# SCH_PHOENIX_-_PCB-3.net
KiCad netlist of a schematic drawn in EasyEDA
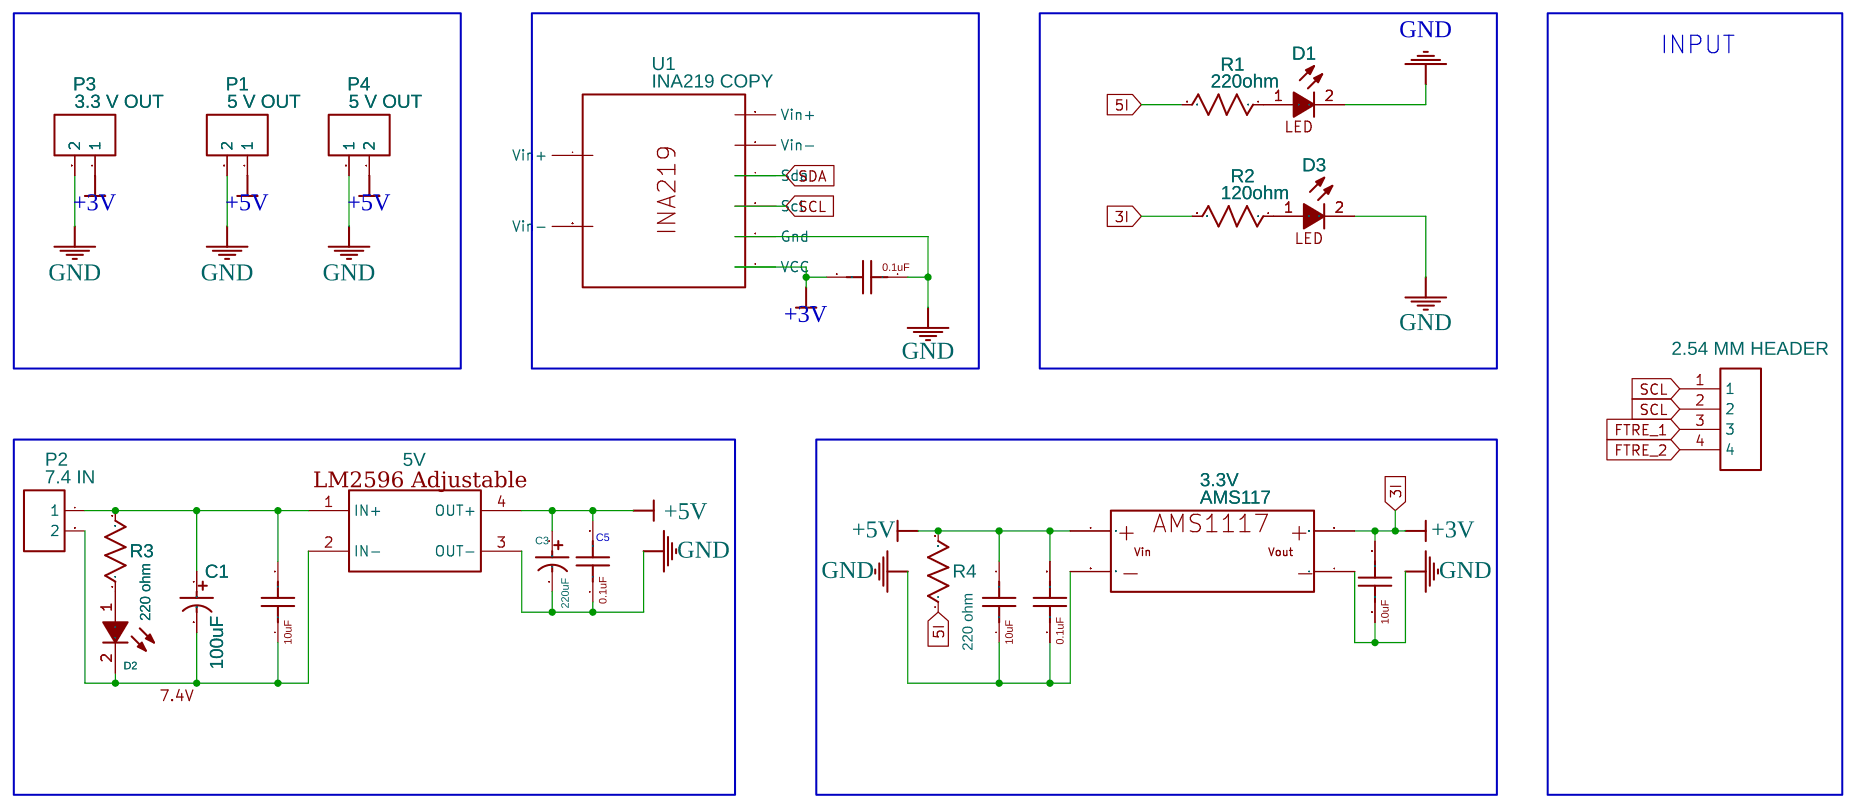
[diagram p0: schematic sheet]

(export (version "E")
  (design (tool "Eeschema 10.0.6"))
  (components
    (comp (ref "3.3V") (value "AMS117") (libsource (lib "") (part "AMS117")))
    (comp (ref "5V") (value "LM2596 ADJ COPY") (libsource (lib "") (part "BuckConverters_LM2596_Adj")))
    (comp (ref "C1")
      (value "100uF")
      (fields
        (field (name "Manufacturer Part") "KM476M016D11RR0VH2FP0")
        (field (name "Manufacturer") "CX(承兴)")
      )
      (libsource (lib "") (part "capacitor 680uF"))
    )
    (comp (ref "C2") (value "22PF CERAMIC CAPACITOR") (libsource (lib "") (part "22PF CERAMIC CAPACITOR")))
    (comp (ref "C3")
      (value "220uF")
      (fields
        (field (name "Manufacturer Part") "KM476M016D11RR0VH2FP0")
        (field (name "Manufacturer") "CX(承兴)")
      )
      (libsource (lib "") (part "capacitor 680uF"))
    )
    (comp (ref "C4") (value "22PF CERAMIC CAPACITOR") (libsource (lib "") (part "22PF CERAMIC CAPACITOR_2")))
    (comp (ref "C5") (value "22PF CERAMIC CAPACITOR") (libsource (lib "") (part "22PF CERAMIC CAPACITOR")))
    (comp (ref "C6") (value "22PF CERAMIC CAPACITOR") (libsource (lib "") (part "22PF CERAMIC CAPACITOR")))
    (comp (ref "C7") (value "22PF CERAMIC CAPACITOR") (libsource (lib "") (part "22PF CERAMIC CAPACITOR_2")))
    (comp (ref "C8") (value "22PF CERAMIC CAPACITOR") (libsource (lib "") (part "22PF CERAMIC CAPACITOR_1")))
    (comp (ref "D1")
      (value "LED")
      (fields (field (name "Manufacturer Part") "5600") (field (name "Manufacturer") "VccLite"))
      (libsource (lib "") (part "LED"))
    )
    (comp (ref "D2")
      (value "LED")
      (fields (field (name "Manufacturer Part") "5600") (field (name "Manufacturer") "VccLite"))
      (libsource (lib "") (part "LED_1"))
    )
    (comp (ref "D3")
      (value "LED")
      (fields (field (name "Manufacturer Part") "5600") (field (name "Manufacturer") "VccLite"))
      (libsource (lib "") (part "LED"))
    )
    (comp (ref "H1")
      (value "2.54 MM HEADER")
      (fields (field (name "Manufacturer Part") "2211S-04G") (field (name "Manufacturer") "MULTICOMP PRO"))
      (libsource (lib "") (part "B2B 2.54 MM HEADER"))
    )
    (comp (ref "P1") (value "5 V OUT") (libsource (lib "") (part "CONN-TH_2P-P5.00")))
    (comp (ref "P2") (value "7.4 IN") (libsource (lib "") (part "CONN-TH_2P-P5.00_2")))
    (comp (ref "P3") (value "3.3 V OUT") (libsource (lib "") (part "CONN-TH_2P-P5.00")))
    (comp (ref "P4") (value "5 V OUT") (libsource (lib "") (part "CONN-TH_2P-P5.00_1")))
    (comp (ref "R1") (value "220ohm") (libsource (lib "") (part "R_0603_US_1")))
    (comp (ref "R2") (value "120ohm") (libsource (lib "") (part "R_0603_US_1")))
    (comp (ref "R3") (value "220 ohm") (libsource (lib "") (part "R_0603_US")))
    (comp (ref "R4") (value "220 ohm") (libsource (lib "") (part "R_0603_US")))
    (comp (ref "U1")
      (value "INA219 COPY")
      (fields (field (name "Manufacturer Part") "INA219"))
      (libsource (lib "") (part "INA219 COPY"))
    )
  )
  (nets
    (net (code "1") (name "+5V") (class "Default")
      (node (ref "3.3V") (pin "1") (pinfunction "1_1") (pintype "unspecified"))
      (node (ref "5V") (pin "4") (pinfunction "OUT+_4") (pintype "unspecified"))
      (node (ref "C2") (pin "2") (pinfunction "2_2") (pintype "unspecified"))
      (node (ref "C3") (pin "1") (pinfunction "1_1") (pintype "unspecified"))
      (node (ref "C4") (pin "2") (pinfunction "2_2") (pintype "unspecified"))
      (node (ref "C7") (pin "2") (pinfunction "2_2") (pintype "unspecified"))
      (node (ref "P1") (pin "1") (pinfunction "1_1") (pintype "unspecified"))
      (node (ref "P4") (pin "1") (pinfunction "2_1") (pintype "unspecified"))
      (node (ref "R4") (pin "2") (pinfunction "2_2") (pintype "unspecified"))
    )
    (net (code "2") (name "3I") (class "Default")
      (node (ref "3.3V") (pin "3") (pinfunction "3_3") (pintype "unspecified"))
      (node (ref "C5") (pin "2") (pinfunction "2_2") (pintype "unspecified"))
      (node (ref "C8") (pin "2") (pinfunction "2_2") (pintype "unspecified"))
      (node (ref "P3") (pin "1") (pinfunction "1_1") (pintype "unspecified"))
      (node (ref "R2") (pin "2") (pinfunction "2_2") (pintype "unspecified"))
      (node (ref "U1") (pin "1") (pinfunction "VCC_1") (pintype "unspecified"))
    )
    (net (code "3") (name "5I") (class "Default")
      (node (ref "R1") (pin "2") (pinfunction "2_2") (pintype "unspecified"))
      (node (ref "R4") (pin "1") (pinfunction "1_1") (pintype "unspecified"))
    )
    (net (code "4") (name "FTRE_1") (class "Default")
      (node (ref "H1") (pin "3") (pinfunction "3_3") (pintype "unspecified"))
    )
    (net (code "5") (name "FTRE_2") (class "Default")
      (node (ref "H1") (pin "4") (pinfunction "4_4") (pintype "unspecified"))
    )
    (net (code "6") (name "GND") (class "Default")
      (node (ref "3.3V") (pin "2") (pinfunction "2_2") (pintype "unspecified"))
      (node (ref "3.3V") (pin "4") (pinfunction "4_4") (pintype "unspecified"))
      (node (ref "5V") (pin "3") (pinfunction "OUT-_3") (pintype "unspecified"))
      (node (ref "C2") (pin "1") (pinfunction "1_1") (pintype "unspecified"))
      (node (ref "C3") (pin "2") (pinfunction "2_2") (pintype "unspecified"))
      (node (ref "C4") (pin "1") (pinfunction "1_1") (pintype "unspecified"))
      (node (ref "C5") (pin "1") (pinfunction "1_1") (pintype "unspecified"))
      (node (ref "C7") (pin "1") (pinfunction "1_1") (pintype "unspecified"))
      (node (ref "C8") (pin "1") (pinfunction "1_1") (pintype "unspecified"))
      (node (ref "D1") (pin "2") (pinfunction "K_2") (pintype "unspecified"))
      (node (ref "D3") (pin "2") (pinfunction "K_2") (pintype "unspecified"))
      (node (ref "P1") (pin "2") (pinfunction "2_2") (pintype "unspecified"))
      (node (ref "P3") (pin "2") (pinfunction "2_2") (pintype "unspecified"))
      (node (ref "P4") (pin "2") (pinfunction "1_2") (pintype "unspecified"))
      (node (ref "U1") (pin "2") (pinfunction "Gnd_2") (pintype "unspecified"))
    )
    (net (code "7") (name "Net-(5V-IN+)") (class "Default")
      (node (ref "5V") (pin "1") (pinfunction "IN+_1") (pintype "unspecified"))
      (node (ref "C1") (pin "1") (pinfunction "1_1") (pintype "unspecified"))
      (node (ref "C6") (pin "2") (pinfunction "2_2") (pintype "unspecified"))
      (node (ref "P2") (pin "1") (pinfunction "1_1") (pintype "unspecified"))
      (node (ref "R3") (pin "2") (pinfunction "2_2") (pintype "unspecified"))
    )
    (net (code "8") (name "Net-(5V-IN-)") (class "Default")
      (node (ref "5V") (pin "2") (pinfunction "IN-_2") (pintype "unspecified"))
      (node (ref "C1") (pin "2") (pinfunction "2_2") (pintype "unspecified"))
      (node (ref "C6") (pin "1") (pinfunction "1_1") (pintype "unspecified"))
      (node (ref "D2") (pin "2") (pinfunction "K_2") (pintype "unspecified"))
      (node (ref "P2") (pin "2") (pinfunction "2_2") (pintype "unspecified"))
    )
    (net (code "9") (name "Net-(D1-A)") (class "Default")
      (node (ref "D1") (pin "1") (pinfunction "A_1") (pintype "unspecified"))
      (node (ref "R1") (pin "1") (pinfunction "1_1") (pintype "unspecified"))
    )
    (net (code "10") (name "Net-(D2-A)") (class "Default")
      (node (ref "D2") (pin "1") (pinfunction "A_1") (pintype "unspecified"))
      (node (ref "R3") (pin "1") (pinfunction "1_1") (pintype "unspecified"))
    )
    (net (code "11") (name "Net-(D3-A)") (class "Default")
      (node (ref "D3") (pin "1") (pinfunction "A_1") (pintype "unspecified"))
      (node (ref "R2") (pin "1") (pinfunction "1_1") (pintype "unspecified"))
    )
    (net (code "12") (name "SCL") (class "Default")
      (node (ref "H1") (pin "1") (pinfunction "1_1") (pintype "unspecified"))
      (node (ref "H1") (pin "2") (pinfunction "2_2") (pintype "unspecified"))
      (node (ref "U1") (pin "3") (pinfunction "Scl_3") (pintype "unspecified"))
    )
    (net (code "13") (name "SDA") (class "Default")
      (node (ref "U1") (pin "4") (pinfunction "Sda_4") (pintype "unspecified"))
    )
    (net (code "14") (name "unconnected-(U1-Vin+-Pad6)") (class "Default")
      (node (ref "U1") (pin "6") (pinfunction "Vin+_6") (pintype "unspecified"))
    )
    (net (code "15") (name "unconnected-(U1-Vin+-Pad7)") (class "Default")
      (node (ref "U1") (pin "7") (pinfunction "Vin+_7") (pintype "unspecified"))
    )
    (net (code "16") (name "unconnected-(U1-Vin--Pad5)") (class "Default")
      (node (ref "U1") (pin "5") (pinfunction "Vin-_5") (pintype "unspecified"))
    )
    (net (code "17") (name "unconnected-(U1-Vin--Pad8)") (class "Default")
      (node (ref "U1") (pin "8") (pinfunction "Vin-_8") (pintype "unspecified"))
    )
  )
)
